# rev_c.net
KiCad netlist of a schematic drawn in EAGLE
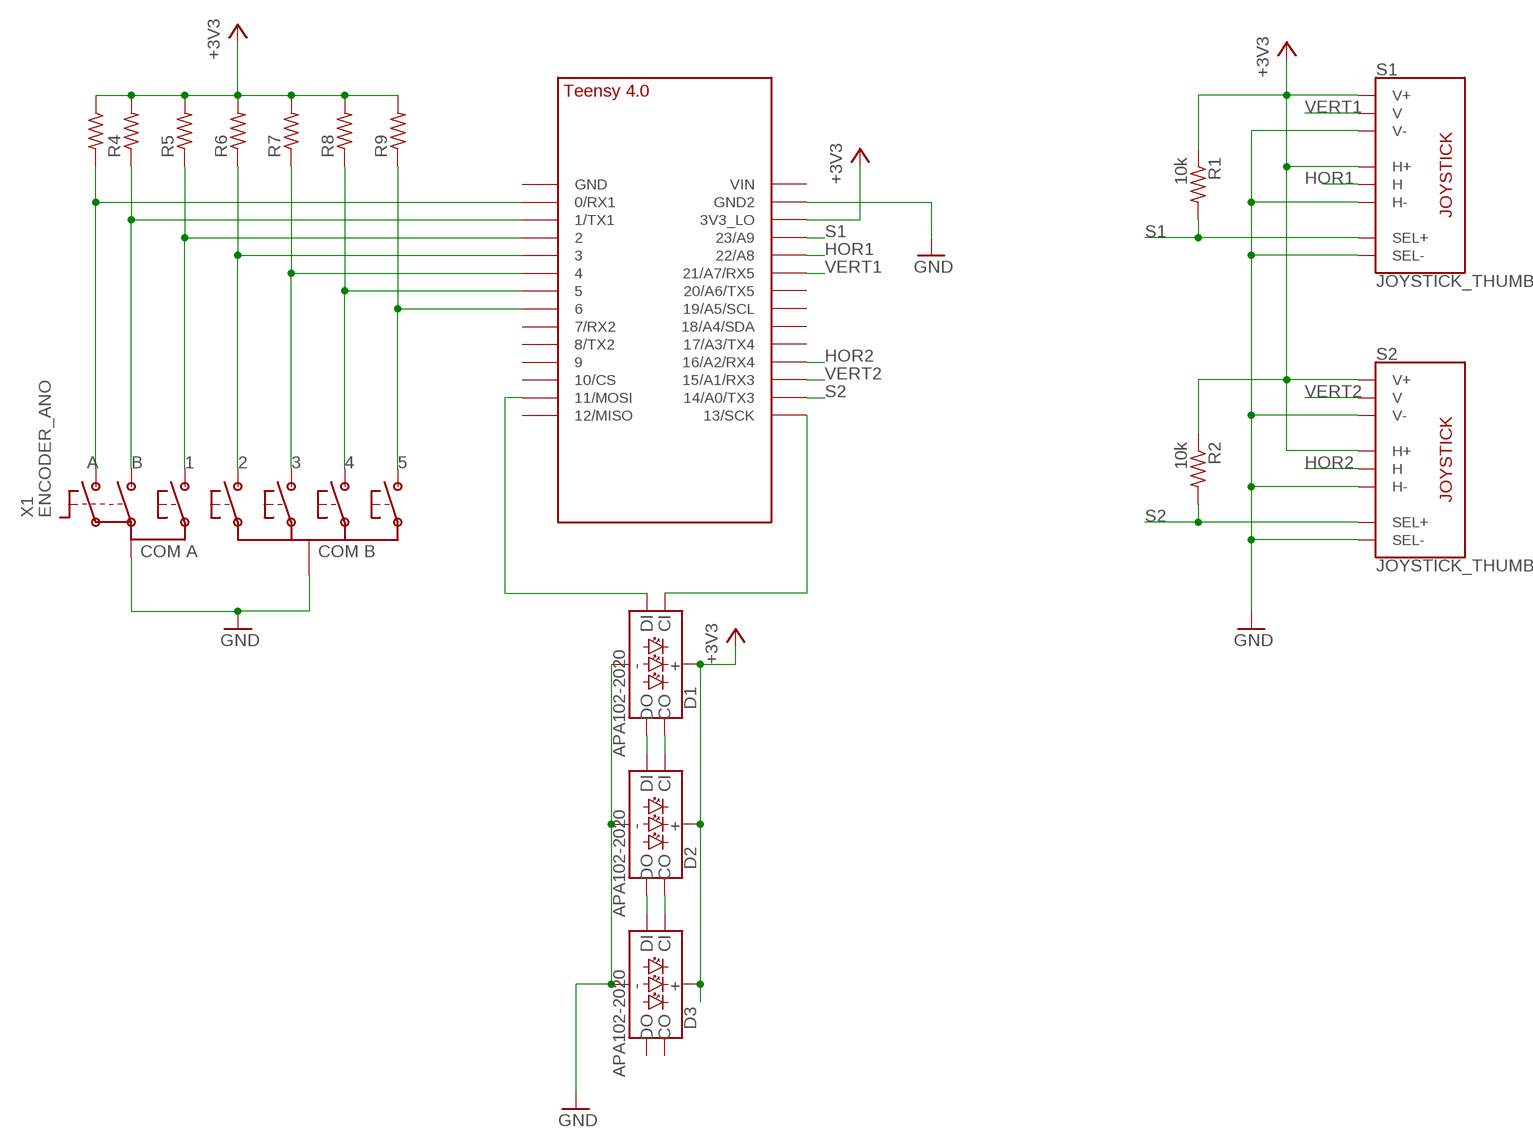
[diagram p0: schematic, sheet 1]

(export (version "E")
  (design (tool "Eeschema 10.0.6"))
  (components
    (comp (ref "D1")
      (value "APA102-2020")
      (footprint "eagle-import:APA102-2020")
      (libsource (lib "eagle-import") (part "APA102-2020"))
    )
    (comp (ref "D2")
      (value "APA102-2020")
      (footprint "eagle-import:APA102-2020")
      (libsource (lib "eagle-import") (part "APA102-2020"))
    )
    (comp (ref "D3")
      (value "APA102-2020")
      (footprint "eagle-import:APA102-2020")
      (libsource (lib "eagle-import") (part "APA102-2020"))
    )
    (comp (ref "MCU")
      (value "TEENSY_4.0-NOBOTTOM")
      (footprint "eagle-import:TEENSY_4.0-NOBOTTOM")
      (libsource (lib "eagle-import") (part "TEENSY_4.0-NOBOTTOM"))
    )
    (comp (ref "R1")
      (value "10k")
      (footprint "eagle-import:R0603")
      (libsource (lib "eagle-import") (part "R-US_R0603"))
    )
    (comp (ref "R2")
      (value "10k")
      (footprint "eagle-import:R0603")
      (libsource (lib "eagle-import") (part "R-US_R0603"))
    )
    (comp (ref "R3")
      (value "10k")
      (footprint "eagle-import:R0603")
      (libsource (lib "eagle-import") (part "R-US_R0603"))
    )
    (comp (ref "R4")
      (value "R-US_R0603")
      (footprint "eagle-import:R0603")
      (libsource (lib "eagle-import") (part "R-US_R0603"))
    )
    (comp (ref "R5")
      (value "R-US_R0603")
      (footprint "eagle-import:R0603")
      (libsource (lib "eagle-import") (part "R-US_R0603"))
    )
    (comp (ref "R6")
      (value "R-US_R0603")
      (footprint "eagle-import:R0603")
      (libsource (lib "eagle-import") (part "R-US_R0603"))
    )
    (comp (ref "R7")
      (value "R-US_R0603")
      (footprint "eagle-import:R0603")
      (libsource (lib "eagle-import") (part "R-US_R0603"))
    )
    (comp (ref "R8")
      (value "R-US_R0603")
      (footprint "eagle-import:R0603")
      (libsource (lib "eagle-import") (part "R-US_R0603"))
    )
    (comp (ref "R9")
      (value "R-US_R0603")
      (footprint "eagle-import:R0603")
      (libsource (lib "eagle-import") (part "R-US_R0603"))
    )
    (comp (ref "S1")
      (value "JOYSTICK_THUMB")
      (footprint "eagle-import:JOYSTICK")
      (libsource (lib "eagle-import") (part "JOYSTICK_THUMB"))
    )
    (comp (ref "S2")
      (value "JOYSTICK_THUMB")
      (footprint "eagle-import:JOYSTICK")
      (libsource (lib "eagle-import") (part "JOYSTICK_THUMB"))
    )
    (comp (ref "X1")
      (value "ENCODER_ANO")
      (footprint "eagle-import:ENCODER_ANO")
      (libsource (lib "eagle-import") (part "ENCODER_ANO"))
    )
  )
  (nets
    (net (code "1") (name "+3V3") (class "Default")
      (node (ref "D1") (pin "VDD") (pinfunction "VCC_VDD") (pintype "bidirectional"))
      (node (ref "D2") (pin "VDD") (pinfunction "VCC_VDD") (pintype "bidirectional"))
      (node (ref "D3") (pin "VDD") (pinfunction "VCC_VDD") (pintype "bidirectional"))
      (node (ref "MCU") (pin "3V3_LO") (pinfunction "3V3_LO_3V3_LO") (pintype "bidirectional"))
      (node (ref "R1") (pin "1") (pinfunction "1_1") (pintype "passive"))
      (node (ref "R2") (pin "1") (pinfunction "1_1") (pintype "passive"))
      (node (ref "R3") (pin "1") (pinfunction "1_1") (pintype "passive"))
      (node (ref "R4") (pin "2") (pinfunction "2_2") (pintype "passive"))
      (node (ref "R5") (pin "2") (pinfunction "2_2") (pintype "passive"))
      (node (ref "R6") (pin "2") (pinfunction "2_2") (pintype "passive"))
      (node (ref "R7") (pin "2") (pinfunction "2_2") (pintype "passive"))
      (node (ref "R8") (pin "2") (pinfunction "2_2") (pintype "passive"))
      (node (ref "R9") (pin "2") (pinfunction "2_2") (pintype "passive"))
      (node (ref "S1") (pin "H1") (pinfunction "H+_H1") (pintype "bidirectional"))
      (node (ref "S1") (pin "V1") (pinfunction "V+_V1") (pintype "bidirectional"))
      (node (ref "S2") (pin "H1") (pinfunction "H+_H1") (pintype "bidirectional"))
      (node (ref "S2") (pin "V1") (pinfunction "V+_V1") (pintype "bidirectional"))
    )
    (net (code "2") (name "/HOR1") (class "Default")
      (node (ref "MCU") (pin "22/A8") (pinfunction "22/A8_22/A8") (pintype "bidirectional"))
      (node (ref "S1") (pin "H2") (pinfunction "H_H2") (pintype "bidirectional"))
    )
    (net (code "3") (name "/HOR2") (class "Default")
      (node (ref "MCU") (pin "16/A2") (pinfunction "16/A2/RX4_16/A2") (pintype "bidirectional"))
      (node (ref "S2") (pin "H2") (pinfunction "H_H2") (pintype "bidirectional"))
    )
    (net (code "4") (name "/S1") (class "Default")
      (node (ref "MCU") (pin "23/A9") (pinfunction "23/A9_23/A9") (pintype "bidirectional"))
      (node (ref "R1") (pin "2") (pinfunction "2_2") (pintype "passive"))
      (node (ref "S1") (pin "B1A") (pinfunction "SEL+_B1A") (pintype "bidirectional"))
    )
    (net (code "5") (name "/S2") (class "Default")
      (node (ref "MCU") (pin "14/A0") (pinfunction "14/A0/TX3_14/A0") (pintype "bidirectional"))
      (node (ref "R2") (pin "2") (pinfunction "2_2") (pintype "passive"))
      (node (ref "S2") (pin "B1A") (pinfunction "SEL+_B1A") (pintype "bidirectional"))
    )
    (net (code "6") (name "/VERT1") (class "Default")
      (node (ref "MCU") (pin "21/A7") (pinfunction "21/A7/RX5_21/A7") (pintype "bidirectional"))
      (node (ref "S1") (pin "V2") (pinfunction "V_V2") (pintype "bidirectional"))
    )
    (net (code "7") (name "/VERT2") (class "Default")
      (node (ref "MCU") (pin "15/A1") (pinfunction "15/A1/RX3_15/A1") (pintype "bidirectional"))
      (node (ref "S2") (pin "V2") (pinfunction "V_V2") (pintype "bidirectional"))
    )
    (net (code "8") (name "GND") (class "Default")
      (node (ref "D1") (pin "GND") (pinfunction "GND_GND") (pintype "bidirectional"))
      (node (ref "D2") (pin "GND") (pinfunction "GND_GND") (pintype "bidirectional"))
      (node (ref "D3") (pin "GND") (pinfunction "GND_GND") (pintype "bidirectional"))
      (node (ref "MCU") (pin "GND2") (pinfunction "GND2_GND2") (pintype "bidirectional"))
      (node (ref "S1") (pin "B2A") (pinfunction "SEL-_B2A") (pintype "bidirectional"))
      (node (ref "S1") (pin "H3") (pinfunction "H-_H3") (pintype "bidirectional"))
      (node (ref "S1") (pin "V3") (pinfunction "V-_V3") (pintype "bidirectional"))
      (node (ref "S2") (pin "B2A") (pinfunction "SEL-_B2A") (pintype "bidirectional"))
      (node (ref "S2") (pin "H3") (pinfunction "H-_H3") (pintype "bidirectional"))
      (node (ref "S2") (pin "V3") (pinfunction "V-_V3") (pintype "bidirectional"))
      (node (ref "X1") (pin "COM_A") (pinfunction "COMA_COM_A") (pintype "passive"))
      (node (ref "X1") (pin "COM_B") (pinfunction "COM_B_COM_B") (pintype "passive"))
    )
    (net (code "9") (name "Net-(D1-CI)") (class "Default")
      (node (ref "D1") (pin "CKI") (pinfunction "CI_CKI") (pintype "bidirectional"))
      (node (ref "MCU") (pin "13/SCK") (pinfunction "13/SCK_13/SCK") (pintype "bidirectional"))
    )
    (net (code "10") (name "Net-(D1-CO)") (class "Default")
      (node (ref "D1") (pin "CKO") (pinfunction "CO_CKO") (pintype "bidirectional"))
      (node (ref "D2") (pin "CKI") (pinfunction "CI_CKI") (pintype "bidirectional"))
    )
    (net (code "11") (name "Net-(D1-DI)") (class "Default")
      (node (ref "D1") (pin "SDI") (pinfunction "DI_SDI") (pintype "bidirectional"))
      (node (ref "MCU") (pin "11/MOSI") (pinfunction "11/MOSI_11/MOSI") (pintype "bidirectional"))
    )
    (net (code "12") (name "Net-(D1-DO)") (class "Default")
      (node (ref "D1") (pin "SDO") (pinfunction "DO_SDO") (pintype "bidirectional"))
      (node (ref "D2") (pin "SDI") (pinfunction "DI_SDI") (pintype "bidirectional"))
    )
    (net (code "13") (name "Net-(D2-CO)") (class "Default")
      (node (ref "D2") (pin "CKO") (pinfunction "CO_CKO") (pintype "bidirectional"))
      (node (ref "D3") (pin "CKI") (pinfunction "CI_CKI") (pintype "bidirectional"))
    )
    (net (code "14") (name "Net-(D2-DO)") (class "Default")
      (node (ref "D2") (pin "SDO") (pinfunction "DO_SDO") (pintype "bidirectional"))
      (node (ref "D3") (pin "SDI") (pinfunction "DI_SDI") (pintype "bidirectional"))
    )
    (net (code "15") (name "Net-(MCU-0{slash}RX1)") (class "Default")
      (node (ref "MCU") (pin "0/RX") (pinfunction "0/RX1_0/RX") (pintype "bidirectional"))
      (node (ref "R3") (pin "2") (pinfunction "2_2") (pintype "passive"))
      (node (ref "X1") (pin "A") (pinfunction "A_A") (pintype "passive"))
    )
    (net (code "16") (name "Net-(MCU-1{slash}TX1)") (class "Default")
      (node (ref "MCU") (pin "1/TX") (pinfunction "1/TX1_1/TX") (pintype "bidirectional"))
      (node (ref "R4") (pin "1") (pinfunction "1_1") (pintype "passive"))
      (node (ref "X1") (pin "B") (pinfunction "B_B") (pintype "passive"))
    )
    (net (code "17") (name "Net-(MCU-3)") (class "Default")
      (node (ref "MCU") (pin "3/CANTX") (pinfunction "3_3/CANTX") (pintype "bidirectional"))
      (node (ref "R6") (pin "1") (pinfunction "1_1") (pintype "passive"))
      (node (ref "X1") (pin "S2") (pinfunction "S2_S2") (pintype "passive"))
    )
    (net (code "18") (name "Net-(MCU-4)") (class "Default")
      (node (ref "MCU") (pin "4/CANRX") (pinfunction "4_4/CANRX") (pintype "bidirectional"))
      (node (ref "R7") (pin "1") (pinfunction "1_1") (pintype "passive"))
      (node (ref "X1") (pin "S3") (pinfunction "S3_S3") (pintype "passive"))
    )
    (net (code "19") (name "Net-(MCU-Pad5)") (class "Default")
      (node (ref "MCU") (pin "5") (pinfunction "5_5") (pintype "bidirectional"))
      (node (ref "R8") (pin "1") (pinfunction "1_1") (pintype "passive"))
      (node (ref "X1") (pin "S4") (pinfunction "S4_S4") (pintype "passive"))
    )
    (net (code "20") (name "Net-(MCU-Pad6)") (class "Default")
      (node (ref "MCU") (pin "6") (pinfunction "6_6") (pintype "bidirectional"))
      (node (ref "R9") (pin "1") (pinfunction "1_1") (pintype "passive"))
      (node (ref "X1") (pin "S5") (pinfunction "S5_S5") (pintype "passive"))
    )
    (net (code "21") (name "Net-(X1-1)") (class "Default")
      (node (ref "MCU") (pin "2") (pinfunction "2_2") (pintype "bidirectional"))
      (node (ref "R5") (pin "1") (pinfunction "1_1") (pintype "passive"))
      (node (ref "X1") (pin "S1") (pinfunction "1_S1") (pintype "passive"))
    )
    (net (code "22") (name "unconnected-(D3-CO-PadCKO)") (class "Default")
      (node (ref "D3") (pin "CKO") (pinfunction "CO_CKO") (pintype "bidirectional"))
    )
    (net (code "23") (name "unconnected-(D3-DO-PadSDO)") (class "Default")
      (node (ref "D3") (pin "SDO") (pinfunction "DO_SDO") (pintype "bidirectional"))
    )
    (net (code "24") (name "unconnected-(MCU-7{slash}RX2-Pad7)") (class "Default")
      (node (ref "MCU") (pin "7") (pinfunction "7/RX2_7") (pintype "bidirectional"))
    )
    (net (code "25") (name "unconnected-(MCU-8{slash}TX2-Pad8)") (class "Default")
      (node (ref "MCU") (pin "8") (pinfunction "8/TX2_8") (pintype "bidirectional"))
    )
    (net (code "26") (name "unconnected-(MCU-9-Pad9{slash}CS)") (class "Default")
      (node (ref "MCU") (pin "9/CS") (pinfunction "9_9/CS") (pintype "bidirectional"))
    )
    (net (code "27") (name "unconnected-(MCU-17{slash}A3{slash}TX4-Pad17{slash}A3)") (class "Default")
      (node (ref "MCU") (pin "17/A3") (pinfunction "17/A3/TX4_17/A3") (pintype "bidirectional"))
    )
    (net (code "28") (name "unconnected-(MCU-20{slash}A6{slash}TX5-Pad20{slash}A6)") (class "Default")
      (node (ref "MCU") (pin "20/A6") (pinfunction "20/A6/TX5_20/A6") (pintype "bidirectional"))
    )
    (net (code "29") (name "unconnected-(MCU-Pad10{slash}CS)") (class "Default")
      (node (ref "MCU") (pin "10/CS") (pinfunction "10/CS_10/CS") (pintype "bidirectional"))
    )
    (net (code "30") (name "unconnected-(MCU-Pad12{slash}MISO)") (class "Default")
      (node (ref "MCU") (pin "12/MISO") (pinfunction "12/MISO_12/MISO") (pintype "bidirectional"))
    )
    (net (code "31") (name "unconnected-(MCU-Pad18{slash}A4{slash}SDA)") (class "Default")
      (node (ref "MCU") (pin "18/A4/SDA") (pinfunction "18/A4/SDA_18/A4/SDA") (pintype "bidirectional"))
    )
    (net (code "32") (name "unconnected-(MCU-Pad19{slash}A5{slash}SCL)") (class "Default")
      (node (ref "MCU") (pin "19/A5/SCL") (pinfunction "19/A5/SCL_19/A5/SCL") (pintype "bidirectional"))
    )
    (net (code "33") (name "unconnected-(MCU-PadGND)") (class "Default")
      (node (ref "MCU") (pin "GND") (pinfunction "GND_GND") (pintype "bidirectional"))
    )
    (net (code "34") (name "unconnected-(MCU-PadVIN)") (class "Default")
      (node (ref "MCU") (pin "VIN") (pinfunction "VIN_VIN") (pintype "bidirectional"))
    )
  )
)
